# nufsr-controller.net
KiCad netlist of a schematic drawn in Altium Designer
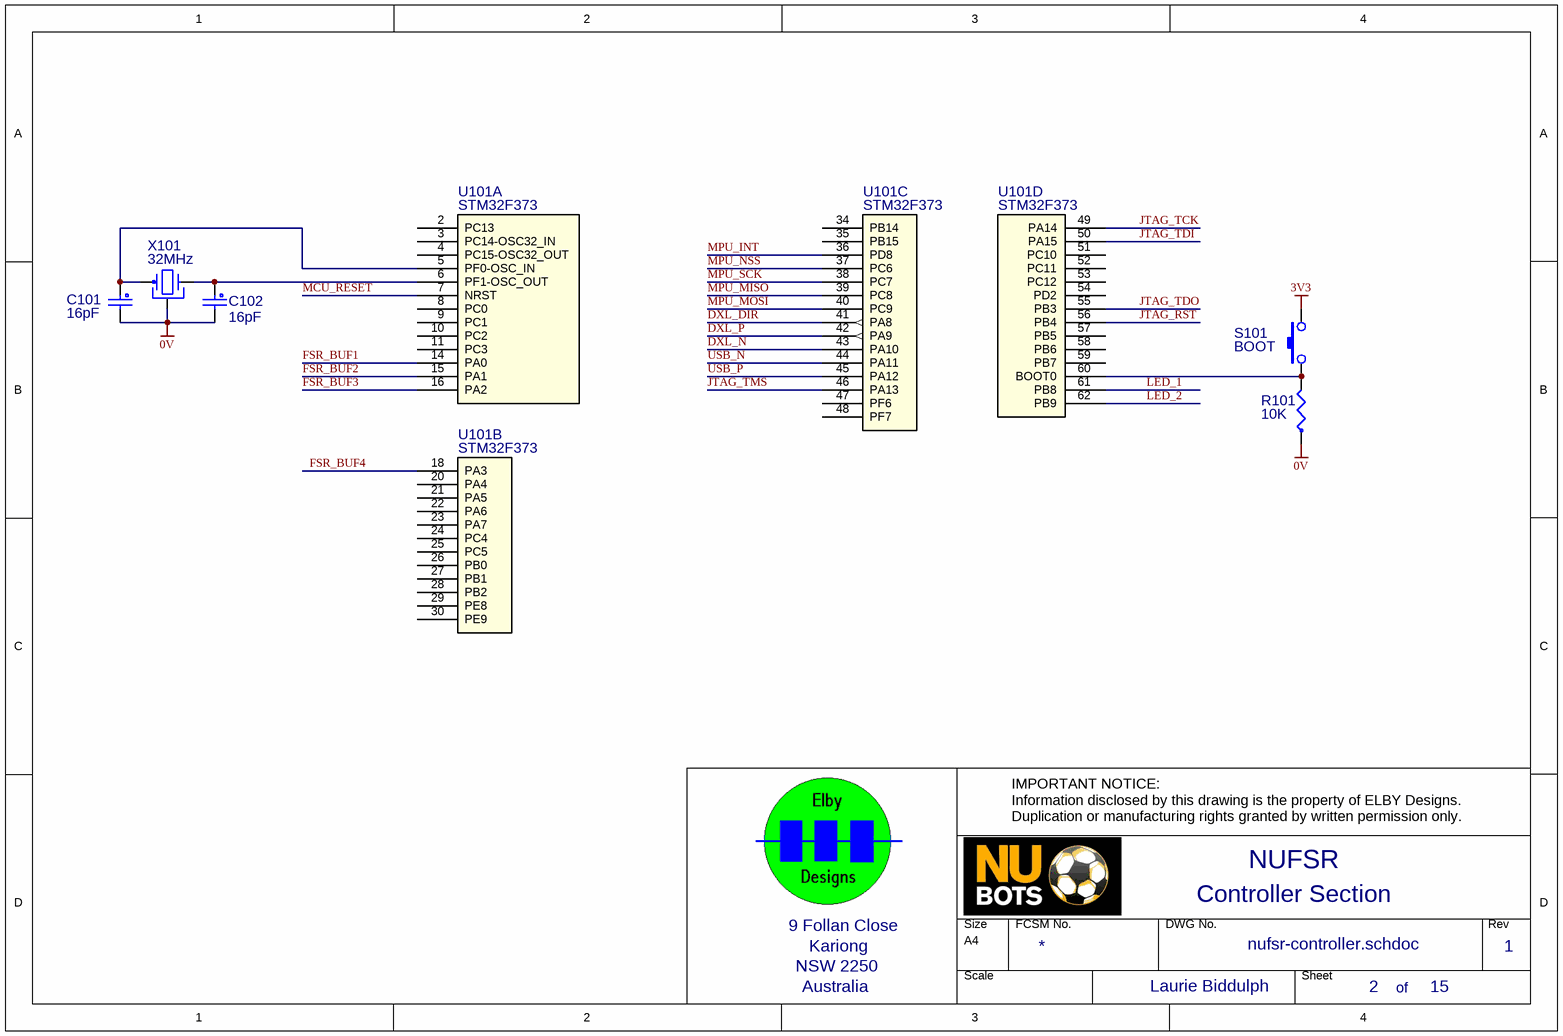
[diagram p0: nufsr-controller.schdoc]

(export (version "E")
  (design (tool "Eeschema 10.0.6"))
  (components
    (comp (ref "C101")
      (value "16pF")
      (footprint "0805(LB)")
      (description "NPO Low K, 50VDC Ceramic Disc")
      (libsource (lib "capacitor") (part "CC-10PF(LB)"))
    )
    (comp (ref "C102")
      (value "16pF")
      (footprint "0805(LB)")
      (description "NPO Low K, 50VDC Ceramic Disc")
      (libsource (lib "capacitor") (part "CC-10PF(LB)"))
    )
    (comp (ref "R101")
      (value "10K")
      (footprint "0603(LB)")
      (description "0.5W 1% Metal Film Resistor")
      (libsource (lib "resistor") (part "RM-10K(LB)"))
    )
    (comp (ref "S101")
      (value "BOOT")
      (footprint "HDR1X2(LB)")
      (description "PCB Push-button Switch")
      (libsource (lib "switches") (part "SW-PB-SPST(LB)"))
    )
    (comp (ref "U101")
      (value "STM32F373")
      (footprint "LQFP-64_10x10(LB)")
      (description "32-bit Microcontroller")
      (fields
        (field (name "MANUFACTURER_PART_NUMBER") "stm32f74xzxt")
        (field (name "COPYRIGHT") "Copyright (C) 2016 Accelerated Designs. All rights reserved")
      )
      (libsource (lib "") (part "STM32F373_1"))
    )
    (comp (ref "X101")
      (value "32MHz")
      (footprint "CRYSTAL-3(LB)")
      (description "24MHz Parallel-cut Crystal - HC49")
      (libsource (lib "passive") (part "XTAL-24MHZ(LB)"))
    )
  )
  (nets
    (net (code "1") (name "/DXL_DIR") (class "Default")
      (node (ref "U101") (pin "41") (pinfunction "PA8_41") (pintype "output"))
    )
    (net (code "2") (name "/DXL_N") (class "Default")
      (node (ref "U101") (pin "43") (pinfunction "PA10_43") (pintype "passive"))
    )
    (net (code "3") (name "/DXL_P") (class "Default")
      (node (ref "U101") (pin "42") (pinfunction "PA9_42") (pintype "output"))
    )
    (net (code "4") (name "/FSR_BUF1") (class "Default")
      (node (ref "U101") (pin "14") (pinfunction "PA0_14") (pintype "passive"))
    )
    (net (code "5") (name "/FSR_BUF2") (class "Default")
      (node (ref "U101") (pin "15") (pinfunction "PA1_15") (pintype "passive"))
    )
    (net (code "6") (name "/FSR_BUF3") (class "Default")
      (node (ref "U101") (pin "16") (pinfunction "PA2_16") (pintype "passive"))
    )
    (net (code "7") (name "/FSR_BUF4") (class "Default")
      (node (ref "U101") (pin "18") (pinfunction "PA3_18") (pintype "passive"))
    )
    (net (code "8") (name "/JTAG_RST") (class "Default")
      (node (ref "U101") (pin "56") (pinfunction "PB4_56") (pintype "passive"))
    )
    (net (code "9") (name "/JTAG_TCK") (class "Default")
      (node (ref "U101") (pin "49") (pinfunction "PA14_49") (pintype "passive"))
    )
    (net (code "10") (name "/JTAG_TDI") (class "Default")
      (node (ref "U101") (pin "50") (pinfunction "PA15_50") (pintype "passive"))
    )
    (net (code "11") (name "/JTAG_TDO") (class "Default")
      (node (ref "U101") (pin "55") (pinfunction "PB3_55") (pintype "passive"))
    )
    (net (code "12") (name "/JTAG_TMS") (class "Default")
      (node (ref "U101") (pin "46") (pinfunction "PA13_46") (pintype "passive"))
    )
    (net (code "13") (name "/LED_1") (class "Default")
      (node (ref "U101") (pin "61") (pinfunction "PB8_61") (pintype "passive"))
    )
    (net (code "14") (name "/LED_2") (class "Default")
      (node (ref "U101") (pin "62") (pinfunction "PB9_62") (pintype "passive"))
    )
    (net (code "15") (name "/MCU_~{RESET}") (class "Default")
      (node (ref "U101") (pin "7") (pinfunction "NRST_7") (pintype "passive"))
    )
    (net (code "16") (name "/MPU_INT") (class "Default")
      (node (ref "U101") (pin "36") (pinfunction "PD8_36") (pintype "passive"))
    )
    (net (code "17") (name "/MPU_MISO") (class "Default")
      (node (ref "U101") (pin "39") (pinfunction "PC8_39") (pintype "passive"))
    )
    (net (code "18") (name "/MPU_MOSI") (class "Default")
      (node (ref "U101") (pin "40") (pinfunction "PC9_40") (pintype "passive"))
    )
    (net (code "19") (name "/MPU_NSS") (class "Default")
      (node (ref "U101") (pin "37") (pinfunction "PC6_37") (pintype "passive"))
    )
    (net (code "20") (name "/MPU_SCK") (class "Default")
      (node (ref "U101") (pin "38") (pinfunction "PC7_38") (pintype "passive"))
    )
    (net (code "21") (name "/USB_N") (class "Default")
      (node (ref "U101") (pin "44") (pinfunction "PA11_44") (pintype "passive"))
    )
    (net (code "22") (name "/USB_P") (class "Default")
      (node (ref "U101") (pin "45") (pinfunction "PA12_45") (pintype "passive"))
    )
    (net (code "23") (name "0V") (class "Default")
      (node (ref "C101") (pin "2") (pintype "passive"))
      (node (ref "C102") (pin "2") (pintype "passive"))
      (node (ref "R101") (pin "1") (pinfunction "1_1") (pintype "passive"))
      (node (ref "X101") (pin "3") (pinfunction "3_3") (pintype "power_in"))
    )
    (net (code "24") (name "3V3") (class "Default")
      (node (ref "S101") (pin "1") (pinfunction "COM_1") (pintype "passive"))
    )
    (net (code "25") (name "Net-(S101-NO)") (class "Default")
      (node (ref "R101") (pin "2") (pinfunction "2_2") (pintype "passive"))
      (node (ref "S101") (pin "2") (pinfunction "NO_2") (pintype "passive"))
      (node (ref "U101") (pin "60") (pinfunction "BOOT0_60") (pintype "passive"))
    )
    (net (code "26") (name "Net-(U101A-PF0-OSC_IN)") (class "Default")
      (node (ref "C101") (pin "1") (pintype "passive"))
      (node (ref "U101") (pin "5") (pinfunction "PF0-OSC_IN_5") (pintype "passive"))
      (node (ref "X101") (pin "1") (pinfunction "1_1") (pintype "passive"))
    )
    (net (code "27") (name "Net-(U101A-PF1-OSC_OUT)") (class "Default")
      (node (ref "C102") (pin "1") (pintype "passive"))
      (node (ref "U101") (pin "6") (pinfunction "PF1-OSC_OUT_6") (pintype "passive"))
      (node (ref "X101") (pin "2") (pinfunction "2_2") (pintype "passive"))
    )
    (net (code "28") (name "unconnected-(U101A-PC0-Pad8)") (class "Default")
      (node (ref "U101") (pin "8") (pinfunction "PC0_8") (pintype "passive"))
    )
    (net (code "29") (name "unconnected-(U101A-PC1-Pad9)") (class "Default")
      (node (ref "U101") (pin "9") (pinfunction "PC1_9") (pintype "passive"))
    )
    (net (code "30") (name "unconnected-(U101A-PC2-Pad10)") (class "Default")
      (node (ref "U101") (pin "10") (pinfunction "PC2_10") (pintype "passive"))
    )
    (net (code "31") (name "unconnected-(U101A-PC3-Pad11)") (class "Default")
      (node (ref "U101") (pin "11") (pinfunction "PC3_11") (pintype "passive"))
    )
    (net (code "32") (name "unconnected-(U101A-PC13-Pad2)") (class "Default")
      (node (ref "U101") (pin "2") (pinfunction "PC13_2") (pintype "passive"))
    )
    (net (code "33") (name "unconnected-(U101A-PC14-OSC32_IN-Pad3)") (class "Default")
      (node (ref "U101") (pin "3") (pinfunction "PC14-OSC32_IN_3") (pintype "passive"))
    )
    (net (code "34") (name "unconnected-(U101A-PC15-OSC32_OUT-Pad4)") (class "Default")
      (node (ref "U101") (pin "4") (pinfunction "PC15-OSC32_OUT_4") (pintype "passive"))
    )
    (net (code "35") (name "unconnected-(U101B-PA4-Pad20)") (class "Default")
      (node (ref "U101") (pin "20") (pinfunction "PA4_20") (pintype "passive"))
    )
    (net (code "36") (name "unconnected-(U101B-PA5-Pad21)") (class "Default")
      (node (ref "U101") (pin "21") (pinfunction "PA5_21") (pintype "passive"))
    )
    (net (code "37") (name "unconnected-(U101B-PA6-Pad22)") (class "Default")
      (node (ref "U101") (pin "22") (pinfunction "PA6_22") (pintype "passive"))
    )
    (net (code "38") (name "unconnected-(U101B-PA7-Pad23)") (class "Default")
      (node (ref "U101") (pin "23") (pinfunction "PA7_23") (pintype "passive"))
    )
    (net (code "39") (name "unconnected-(U101B-PB0-Pad26)") (class "Default")
      (node (ref "U101") (pin "26") (pinfunction "PB0_26") (pintype "passive"))
    )
    (net (code "40") (name "unconnected-(U101B-PB1-Pad27)") (class "Default")
      (node (ref "U101") (pin "27") (pinfunction "PB1_27") (pintype "passive"))
    )
    (net (code "41") (name "unconnected-(U101B-PB2-Pad28)") (class "Default")
      (node (ref "U101") (pin "28") (pinfunction "PB2_28") (pintype "passive"))
    )
    (net (code "42") (name "unconnected-(U101B-PC4-Pad24)") (class "Default")
      (node (ref "U101") (pin "24") (pinfunction "PC4_24") (pintype "passive"))
    )
    (net (code "43") (name "unconnected-(U101B-PC5-Pad25)") (class "Default")
      (node (ref "U101") (pin "25") (pinfunction "PC5_25") (pintype "passive"))
    )
    (net (code "44") (name "unconnected-(U101B-PE8-Pad29)") (class "Default")
      (node (ref "U101") (pin "29") (pinfunction "PE8_29") (pintype "passive"))
    )
    (net (code "45") (name "unconnected-(U101B-PE9-Pad30)") (class "Default")
      (node (ref "U101") (pin "30") (pinfunction "PE9_30") (pintype "passive"))
    )
    (net (code "46") (name "unconnected-(U101C-PB14-Pad34)") (class "Default")
      (node (ref "U101") (pin "34") (pinfunction "PB14_34") (pintype "passive"))
    )
    (net (code "47") (name "unconnected-(U101C-PB15-Pad35)") (class "Default")
      (node (ref "U101") (pin "35") (pinfunction "PB15_35") (pintype "passive"))
    )
    (net (code "48") (name "unconnected-(U101C-PF6-Pad47)") (class "Default")
      (node (ref "U101") (pin "47") (pinfunction "PF6_47") (pintype "passive"))
    )
    (net (code "49") (name "unconnected-(U101C-PF7-Pad48)") (class "Default")
      (node (ref "U101") (pin "48") (pinfunction "PF7_48") (pintype "passive"))
    )
    (net (code "50") (name "unconnected-(U101D-PB5-Pad57)") (class "Default")
      (node (ref "U101") (pin "57") (pinfunction "PB5_57") (pintype "passive"))
    )
    (net (code "51") (name "unconnected-(U101D-PB6-Pad58)") (class "Default")
      (node (ref "U101") (pin "58") (pinfunction "PB6_58") (pintype "passive"))
    )
    (net (code "52") (name "unconnected-(U101D-PB7-Pad59)") (class "Default")
      (node (ref "U101") (pin "59") (pinfunction "PB7_59") (pintype "passive"))
    )
    (net (code "53") (name "unconnected-(U101D-PC10-Pad51)") (class "Default")
      (node (ref "U101") (pin "51") (pinfunction "PC10_51") (pintype "passive"))
    )
    (net (code "54") (name "unconnected-(U101D-PC11-Pad52)") (class "Default")
      (node (ref "U101") (pin "52") (pinfunction "PC11_52") (pintype "passive"))
    )
    (net (code "55") (name "unconnected-(U101D-PC12-Pad53)") (class "Default")
      (node (ref "U101") (pin "53") (pinfunction "PC12_53") (pintype "passive"))
    )
    (net (code "56") (name "unconnected-(U101D-PD2-Pad54)") (class "Default")
      (node (ref "U101") (pin "54") (pinfunction "PD2_54") (pintype "passive"))
    )
  )
)
